# mainboard_wifi_v1_1.net
KiCad netlist of a schematic drawn in Altium Designer
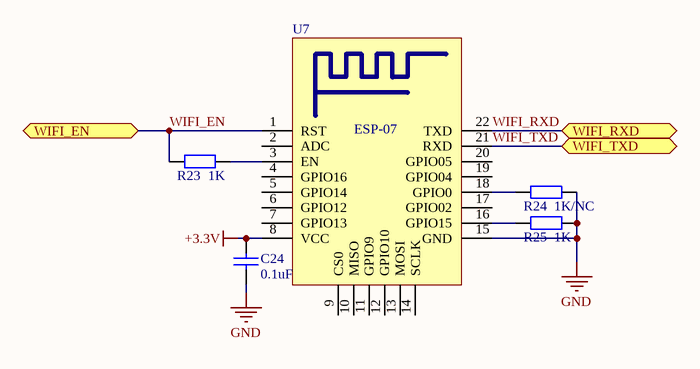
[diagram p0: mainboard_wifi.v1.1.SchDoc]

(export (version "E")
  (design (tool "Eeschema 10.0.6"))
  (components
    (comp (ref "C24")
      (value "0.1uF")
      (footprint "0805")
      (description "Capacitor")
      (libsource (lib "Miscellaneous Devices") (part "Cap"))
    )
    (comp (ref "R23")
      (value "1K")
      (footprint "0805")
      (description "Resistor")
      (libsource (lib "Miscellaneous Devices") (part "Res2"))
    )
    (comp (ref "R24")
      (value "1K/NC")
      (footprint "0805")
      (description "Resistor")
      (libsource (lib "Miscellaneous Devices") (part "Res2"))
    )
    (comp (ref "R25")
      (value "1K")
      (footprint "0805")
      (description "Resistor")
      (libsource (lib "Miscellaneous Devices") (part "Res2"))
    )
    (comp (ref "U7") (value "ESP-07") (footprint "ESP-12F") (libsource (lib "Componet") (part "ESP-12F")))
  )
  (nets
    (net (code "1") (name "+3.3V") (class "Default")
      (node (ref "C24") (pin "2") (pinfunction "2_2") (pintype "passive"))
      (node (ref "U7") (pin "8") (pinfunction "VCC_8") (pintype "passive"))
    )
    (net (code "2") (name "/WIFI_EN") (class "Default")
      (node (ref "R23") (pin "1") (pinfunction "1_1") (pintype "passive"))
      (node (ref "U7") (pin "1") (pinfunction "RST_1") (pintype "passive"))
    )
    (net (code "3") (name "/WIFI_RXD") (class "Default")
      (node (ref "U7") (pin "22") (pinfunction "TXD_22") (pintype "passive"))
    )
    (net (code "4") (name "/WIFI_TXD") (class "Default")
      (node (ref "U7") (pin "21") (pinfunction "RXD_21") (pintype "passive"))
    )
    (net (code "5") (name "GND") (class "Default")
      (node (ref "C24") (pin "1") (pinfunction "1_1") (pintype "passive"))
      (node (ref "R24") (pin "2") (pinfunction "2_2") (pintype "passive"))
      (node (ref "R25") (pin "2") (pinfunction "2_2") (pintype "passive"))
      (node (ref "U7") (pin "15") (pinfunction "GND_15") (pintype "passive"))
    )
    (net (code "6") (name "Net-(U7-EN)") (class "Default")
      (node (ref "R23") (pin "2") (pinfunction "2_2") (pintype "passive"))
      (node (ref "U7") (pin "3") (pinfunction "EN_3") (pintype "passive"))
    )
    (net (code "7") (name "Net-(U7-GPIO0)") (class "Default")
      (node (ref "R24") (pin "1") (pinfunction "1_1") (pintype "passive"))
      (node (ref "U7") (pin "18") (pinfunction "GPIO0_18") (pintype "passive"))
    )
    (net (code "8") (name "Net-(U7-GPIO15)") (class "Default")
      (node (ref "R25") (pin "1") (pinfunction "1_1") (pintype "passive"))
      (node (ref "U7") (pin "16") (pinfunction "GPIO15_16") (pintype "passive"))
    )
    (net (code "9") (name "unconnected-(U7-ADC-Pad2)") (class "Default")
      (node (ref "U7") (pin "2") (pinfunction "ADC_2") (pintype "passive"))
    )
    (net (code "10") (name "unconnected-(U7-CS0-Pad9)") (class "Default")
      (node (ref "U7") (pin "9") (pinfunction "CS0_9") (pintype "passive"))
    )
    (net (code "11") (name "unconnected-(U7-GPIO02-Pad17)") (class "Default")
      (node (ref "U7") (pin "17") (pinfunction "GPIO02_17") (pintype "passive"))
    )
    (net (code "12") (name "unconnected-(U7-GPIO04-Pad19)") (class "Default")
      (node (ref "U7") (pin "19") (pinfunction "GPIO04_19") (pintype "passive"))
    )
    (net (code "13") (name "unconnected-(U7-GPIO05-Pad20)") (class "Default")
      (node (ref "U7") (pin "20") (pinfunction "GPIO05_20") (pintype "passive"))
    )
    (net (code "14") (name "unconnected-(U7-GPIO9-Pad11)") (class "Default")
      (node (ref "U7") (pin "11") (pinfunction "GPIO9_11") (pintype "passive"))
    )
    (net (code "15") (name "unconnected-(U7-GPIO10-Pad12)") (class "Default")
      (node (ref "U7") (pin "12") (pinfunction "GPIO10_12") (pintype "passive"))
    )
    (net (code "16") (name "unconnected-(U7-GPIO12-Pad6)") (class "Default")
      (node (ref "U7") (pin "6") (pinfunction "GPIO12_6") (pintype "passive"))
    )
    (net (code "17") (name "unconnected-(U7-GPIO13-Pad7)") (class "Default")
      (node (ref "U7") (pin "7") (pinfunction "GPIO13_7") (pintype "passive"))
    )
    (net (code "18") (name "unconnected-(U7-GPIO14-Pad5)") (class "Default")
      (node (ref "U7") (pin "5") (pinfunction "GPIO14_5") (pintype "passive"))
    )
    (net (code "19") (name "unconnected-(U7-GPIO16-Pad4)") (class "Default")
      (node (ref "U7") (pin "4") (pinfunction "GPIO16_4") (pintype "passive"))
    )
    (net (code "20") (name "unconnected-(U7-MISO-Pad10)") (class "Default")
      (node (ref "U7") (pin "10") (pinfunction "MISO_10") (pintype "passive"))
    )
    (net (code "21") (name "unconnected-(U7-MOSI-Pad13)") (class "Default")
      (node (ref "U7") (pin "13") (pinfunction "MOSI_13") (pintype "passive"))
    )
    (net (code "22") (name "unconnected-(U7-SCLK-Pad14)") (class "Default")
      (node (ref "U7") (pin "14") (pinfunction "SCLK_14") (pintype "passive"))
    )
  )
)
